# RP2040_Logic_Analyzer.net
KiCad netlist of a schematic drawn in Altium Designer
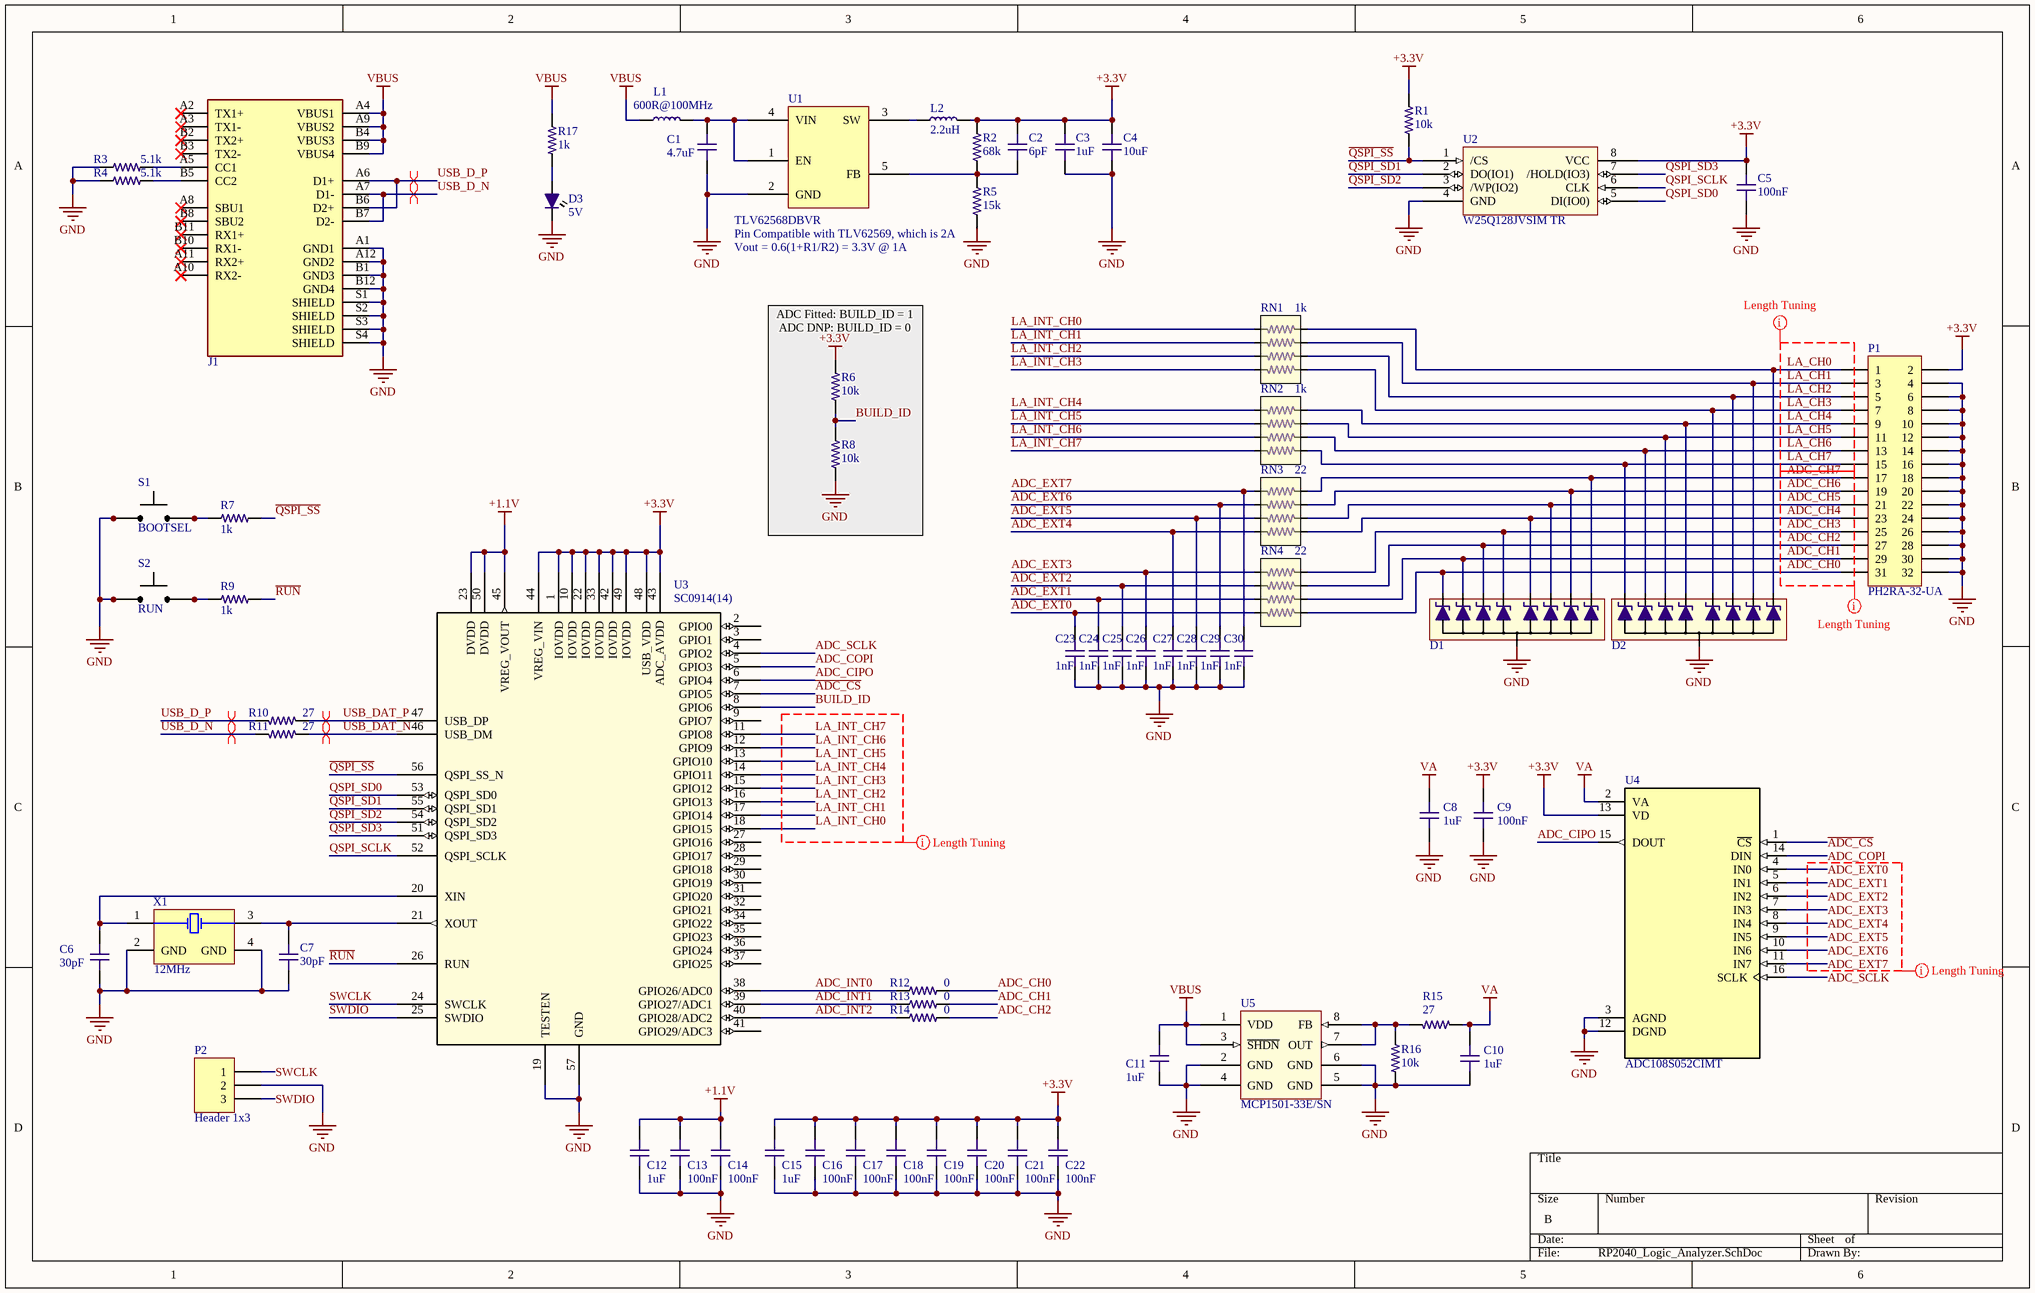
[diagram p0: RP2040_Logic_Analyzer.SchDoc]

(export (version "E")
  (design (tool "Eeschema 10.0.6"))
  (components
    (comp (ref "C1")
      (value "4.7uF")
      (footprint "C0603-HIGH-DENSITY")
      (description "Chip Capacitor, 0603, 4.7uF, 25V, X5R")
      (fields (field (name "Comment") "4.7uF, 25V, X5R, 0603"))
      (libsource (lib "Capacitors") (part "C0603 4.7uF 25V X5R"))
    )
    (comp (ref "C2")
      (value "6pF")
      (footprint "C0603-HIGH-DENSITY")
      (description "CAP CER 6PF 50V C0G/NP0 0603")
      (fields (field (name "Comment") "CL10C060DB8NNNC"))
      (libsource (lib "Capacitors") (part "C0603 6pF 50V C0G"))
    )
    (comp (ref "C3")
      (value "1uF")
      (footprint "C0603-HIGH-DENSITY")
      (description "CAP CER 1UF 25V X7R 0603")
      (fields (field (name "Comment") "C0603 1uF 25V X7R"))
      (libsource (lib "Capacitors") (part "C0603 1uF 25V X7R"))
    )
    (comp (ref "C4")
      (value "10uF")
      (footprint "C0603-HIGH-DENSITY")
      (description "Chip Capacitor, 0603, 10uF, 10V, X5R")
      (fields (field (name "Comment") "C0603 10uF 10V X5R"))
      (libsource (lib "Capacitors") (part "C0603 10uF 10V X5R"))
    )
    (comp (ref "C5")
      (value "100nF")
      (footprint "C0603-HIGH-DENSITY")
      (description "Chip Capacitor, 0603, 100nF, 25V, X7R")
      (fields (field (name "Comment") "C0603 100nF 25V X7R"))
      (libsource (lib "Capacitors") (part "C0603 100nF 25V X7R"))
    )
    (comp (ref "C6")
      (value "30pF")
      (footprint "C0402-HIGH-DENSITY")
      (description "Chip Capacitor, 0402, 30pF, 2%, 50V, C0G")
      (fields (field (name "Comment") "C0402 30pF 50V C0G"))
      (libsource (lib "Capacitors") (part "C0402 30pF 50V C0G"))
    )
    (comp (ref "C7")
      (value "30pF")
      (footprint "C0402-HIGH-DENSITY")
      (description "Chip Capacitor, 0402, 30pF, 2%, 50V, C0G")
      (fields (field (name "Comment") "C0402 30pF 50V C0G"))
      (libsource (lib "Capacitors") (part "C0402 30pF 50V C0G"))
    )
    (comp (ref "C8")
      (value "1uF")
      (footprint "C0603-HIGH-DENSITY")
      (description "CAP CER 1UF 25V X7R 0603")
      (fields (field (name "Comment") "C0603 1uF 25V X7R"))
      (libsource (lib "Capacitors") (part "C0603 1uF 25V X7R"))
    )
    (comp (ref "C9")
      (value "100nF")
      (footprint "C0603-HIGH-DENSITY")
      (description "Chip Capacitor, 0603, 100nF, 25V, X7R")
      (fields (field (name "Comment") "C0603 100nF 25V X7R"))
      (libsource (lib "Capacitors") (part "C0603 100nF 25V X7R"))
    )
    (comp (ref "C10")
      (value "1uF")
      (footprint "C0603-HIGH-DENSITY")
      (description "CAP CER 1UF 25V X7R 0603")
      (fields (field (name "Comment") "C0603 1uF 25V X7R"))
      (libsource (lib "Capacitors") (part "C0603 1uF 25V X7R"))
    )
    (comp (ref "C11")
      (value "1uF")
      (footprint "C0603-HIGH-DENSITY")
      (description "CAP CER 1UF 25V X7R 0603")
      (fields (field (name "Comment") "C0603 1uF 25V X7R"))
      (libsource (lib "Capacitors") (part "C0603 1uF 25V X7R"))
    )
    (comp (ref "C12")
      (value "1uF")
      (footprint "C0603-HIGH-DENSITY")
      (description "CAP CER 1UF 25V X7R 0603")
      (fields (field (name "Comment") "C0603 1uF 25V X7R"))
      (libsource (lib "Capacitors") (part "C0603 1uF 25V X7R"))
    )
    (comp (ref "C13")
      (value "100nF")
      (footprint "C0603-HIGH-DENSITY")
      (description "Chip Capacitor, 0603, 100nF, 25V, X7R")
      (fields (field (name "Comment") "C0603 100nF 25V X7R"))
      (libsource (lib "Capacitors") (part "C0603 100nF 25V X7R"))
    )
    (comp (ref "C14")
      (value "100nF")
      (footprint "C0603-HIGH-DENSITY")
      (description "Chip Capacitor, 0603, 100nF, 25V, X7R")
      (fields (field (name "Comment") "C0603 100nF 25V X7R"))
      (libsource (lib "Capacitors") (part "C0603 100nF 25V X7R"))
    )
    (comp (ref "C15")
      (value "1uF")
      (footprint "C0603-HIGH-DENSITY")
      (description "CAP CER 1UF 25V X7R 0603")
      (fields (field (name "Comment") "C0603 1uF 25V X7R"))
      (libsource (lib "Capacitors") (part "C0603 1uF 25V X7R"))
    )
    (comp (ref "C16")
      (value "100nF")
      (footprint "C0603-HIGH-DENSITY")
      (description "Chip Capacitor, 0603, 100nF, 25V, X7R")
      (fields (field (name "Comment") "C0603 100nF 25V X7R"))
      (libsource (lib "Capacitors") (part "C0603 100nF 25V X7R"))
    )
    (comp (ref "C17")
      (value "100nF")
      (footprint "C0603-HIGH-DENSITY")
      (description "Chip Capacitor, 0603, 100nF, 25V, X7R")
      (fields (field (name "Comment") "C0603 100nF 25V X7R"))
      (libsource (lib "Capacitors") (part "C0603 100nF 25V X7R"))
    )
    (comp (ref "C18")
      (value "100nF")
      (footprint "C0603-HIGH-DENSITY")
      (description "Chip Capacitor, 0603, 100nF, 25V, X7R")
      (fields (field (name "Comment") "C0603 100nF 25V X7R"))
      (libsource (lib "Capacitors") (part "C0603 100nF 25V X7R"))
    )
    (comp (ref "C19")
      (value "100nF")
      (footprint "C0603-HIGH-DENSITY")
      (description "Chip Capacitor, 0603, 100nF, 25V, X7R")
      (fields (field (name "Comment") "C0603 100nF 25V X7R"))
      (libsource (lib "Capacitors") (part "C0603 100nF 25V X7R"))
    )
    (comp (ref "C20")
      (value "100nF")
      (footprint "C0603-HIGH-DENSITY")
      (description "Chip Capacitor, 0603, 100nF, 25V, X7R")
      (fields (field (name "Comment") "C0603 100nF 25V X7R"))
      (libsource (lib "Capacitors") (part "C0603 100nF 25V X7R"))
    )
    (comp (ref "C21")
      (value "100nF")
      (footprint "C0603-HIGH-DENSITY")
      (description "Chip Capacitor, 0603, 100nF, 25V, X7R")
      (fields (field (name "Comment") "C0603 100nF 25V X7R"))
      (libsource (lib "Capacitors") (part "C0603 100nF 25V X7R"))
    )
    (comp (ref "C22")
      (value "100nF")
      (footprint "C0603-HIGH-DENSITY")
      (description "Chip Capacitor, 0603, 100nF, 25V, X7R")
      (fields (field (name "Comment") "C0603 100nF 25V X7R"))
      (libsource (lib "Capacitors") (part "C0603 100nF 25V X7R"))
    )
    (comp (ref "C23")
      (value "1nF")
      (footprint "C0402-IPC")
      (description "Chip Capacitor, 0402, 1nF, 25V, X7R")
      (fields (field (name "Comment") "C0402 1nF 16V X7R"))
      (libsource (lib "Capacitors") (part "C0402 1nF 16V X7R"))
    )
    (comp (ref "C24")
      (value "1nF")
      (footprint "C0402-IPC")
      (description "Chip Capacitor, 0402, 1nF, 25V, X7R")
      (fields (field (name "Comment") "C0402 1nF 16V X7R"))
      (libsource (lib "Capacitors") (part "C0402 1nF 16V X7R"))
    )
    (comp (ref "C25")
      (value "1nF")
      (footprint "C0402-IPC")
      (description "Chip Capacitor, 0402, 1nF, 25V, X7R")
      (fields (field (name "Comment") "C0402 1nF 16V X7R"))
      (libsource (lib "Capacitors") (part "C0402 1nF 16V X7R"))
    )
    (comp (ref "C26")
      (value "1nF")
      (footprint "C0402-IPC")
      (description "Chip Capacitor, 0402, 1nF, 25V, X7R")
      (fields (field (name "Comment") "C0402 1nF 16V X7R"))
      (libsource (lib "Capacitors") (part "C0402 1nF 16V X7R"))
    )
    (comp (ref "C27")
      (value "1nF")
      (footprint "C0402-IPC")
      (description "Chip Capacitor, 0402, 1nF, 25V, X7R")
      (fields (field (name "Comment") "C0402 1nF 16V X7R"))
      (libsource (lib "Capacitors") (part "C0402 1nF 16V X7R"))
    )
    (comp (ref "C28")
      (value "1nF")
      (footprint "C0402-IPC")
      (description "Chip Capacitor, 0402, 1nF, 25V, X7R")
      (fields (field (name "Comment") "C0402 1nF 16V X7R"))
      (libsource (lib "Capacitors") (part "C0402 1nF 16V X7R"))
    )
    (comp (ref "C29")
      (value "1nF")
      (footprint "C0402-IPC")
      (description "Chip Capacitor, 0402, 1nF, 25V, X7R")
      (fields (field (name "Comment") "C0402 1nF 16V X7R"))
      (libsource (lib "Capacitors") (part "C0402 1nF 16V X7R"))
    )
    (comp (ref "C30")
      (value "1nF")
      (footprint "C0402-IPC")
      (description "Chip Capacitor, 0402, 1nF, 25V, X7R")
      (fields (field (name "Comment") "C0402 1nF 16V X7R"))
      (libsource (lib "Capacitors") (part "C0402 1nF 16V X7R"))
    )
    (comp (ref "D1")
      (value "ESD8008MUTAG")
      (footprint "UDFN14_517CN_ONS")
      (description "8.1V (Typ) Clamp 16A Ipp Tvs Diode Surface Mount 14-UDFN (5.5x1.5)")
      (libsource (lib "Diodes") (part "ESD8008MUTAG"))
    )
    (comp (ref "D2")
      (value "ESD8008MUTAG")
      (footprint "UDFN14_517CN_ONS")
      (description "8.1V (Typ) Clamp 16A Ipp Tvs Diode Surface Mount 14-UDFN (5.5x1.5)")
      (libsource (lib "Diodes") (part "ESD8008MUTAG"))
    )
    (comp (ref "D3")
      (value "5V")
      (footprint "LED0603-IPC")
      (description "LED GREEN CLEAR 0603 SMD")
      (libsource (lib "Diodes") (part "LED 0603 Green"))
    )
    (comp (ref "J1")
      (value "USB C")
      (footprint "Molex USB-C")
      (fields
        (field (name "MF") "Molex")
        (field (name "DIGI-KEY_PART_NUMBER") "WM12856CT-ND")
        (field (name "MP") "1054500101")
      )
      (libsource (lib "Connectors") (part "USB C"))
    )
    (comp (ref "L1")
      (value "600R@100MHz")
      (footprint "L0603")
      (description "600 Ohms @ 100MHz 1 Ferrite Bead 0603 (1608 Metric) 500mA 380mOhm")
      (fields (field (name "Comment") "Ferrite Bead"))
      (libsource (lib "Inductors") (part "FB 0603 600R @ 100MHz"))
    )
    (comp (ref "L2")
      (value "2.2uH")
      (footprint "L1008")
      (description "2.2µH Shielded Inductor 2.05A 117mOhm Max 1008 (2520 Metric)")
      (fields (field (name "Comment") "SDEM25201B-2R2MS"))
      (libsource (lib "Inductors") (part "SDEM25201B-2R2MS"))
    )
    (comp (ref "P1")
      (value "PH2RA-32-UA")
      (footprint "Header 2X16 THT RIGHT")
      (description "Header, 16-Pin, Dual row, Right Angle")
      (libsource (lib "Connectors") (part "Header 16X2 Right Angle"))
    )
    (comp (ref "P2")
      (value "Header 1x3")
      (footprint "HEADER 1X3 TH 2.54mm")
      (description "Header, 3-Pin")
      (fields (field (name "PUBLISHER") "Altium Limited"))
      (libsource (lib "Connectors") (part "Header 1x3"))
    )
    (comp (ref "R1")
      (value "10k")
      (footprint "R0603-IPC-10K")
      (description "RES SMD 10K OHM 1% 1/10W 0603")
      (fields (field (name "Comment") "R0603 10K 1%"))
      (libsource (lib "Resistors") (part "R0603 10K 1%"))
    )
    (comp (ref "R2")
      (value "68k")
      (footprint "R0603-HIGH-DENSITY")
      (description "RES SMD 68K OHM 1% 1/5W 0603")
      (fields (field (name "Comment") "R0603 68K 1%"))
      (libsource (lib "Resistors") (part "R0603 68K 0.1%"))
    )
    (comp (ref "R3")
      (value "5.1k")
      (footprint "R0603-IPC-5.1K")
      (description "RES SMD 5.1K OHM 1% 1/10W 0603")
      (fields (field (name "Comment") "R0603 5.1K 1%"))
      (libsource (lib "Resistors") (part "R0603 5.1K 1%"))
    )
    (comp (ref "R4")
      (value "5.1k")
      (footprint "R0603-IPC-5.1K")
      (description "RES SMD 5.1K OHM 1% 1/10W 0603")
      (fields (field (name "Comment") "R0603 5.1K 1%"))
      (libsource (lib "Resistors") (part "R0603 5.1K 1%"))
    )
    (comp (ref "R5")
      (value "15k")
      (footprint "R0603-HIGH-DENSITY")
      (description "RES SMD 15K OHM 1% 1/10W 0603")
      (fields (field (name "Comment") "R0603 15K 1%"))
      (libsource (lib "Resistors") (part "R0603 15K 1%"))
    )
    (comp (ref "R6")
      (value "10k")
      (footprint "R0603-IPC-10K")
      (description "RES SMD 10K OHM 1% 1/10W 0603")
      (fields (field (name "Comment") "R0603 10K 1%"))
      (libsource (lib "Resistors") (part "R0603 10K 1%"))
    )
    (comp (ref "R7")
      (value "1k")
      (footprint "R0603-IPC-1K")
      (description "RES SMD 1K OHM 1% 1/10W 0603")
      (fields (field (name "TOLERANCE") "±1%") (field (name "Comment") "R0603 1K 1%"))
      (libsource (lib "Resistors") (part "R0603 1K 1%"))
    )
    (comp (ref "R8")
      (value "10k")
      (footprint "R0603-IPC-10K")
      (description "RES SMD 10K OHM 1% 1/10W 0603")
      (fields (field (name "Comment") "R0603 10K 1%"))
      (libsource (lib "Resistors") (part "R0603 10K 1%"))
    )
    (comp (ref "R9")
      (value "1k")
      (footprint "R0603-IPC-1K")
      (description "RES SMD 1K OHM 1% 1/10W 0603")
      (fields (field (name "TOLERANCE") "±1%") (field (name "Comment") "R0603 1K 1%"))
      (libsource (lib "Resistors") (part "R0603 1K 1%"))
    )
    (comp (ref "R10")
      (value "27")
      (footprint "R0603-HIGH-DENSITY")
      (description "RES SMD 27 OHM 1% 1/10W 0603")
      (fields (field (name "Comment") "R0603 27R 1%"))
      (libsource (lib "Resistors") (part "R0603 27R 1%"))
    )
    (comp (ref "R11")
      (value "27")
      (footprint "R0603-HIGH-DENSITY")
      (description "RES SMD 27 OHM 1% 1/10W 0603")
      (fields (field (name "Comment") "R0603 27R 1%"))
      (libsource (lib "Resistors") (part "R0603 27R 1%"))
    )
    (comp (ref "R12")
      (value "0")
      (footprint "R0402-HIGH-DENSITY")
      (description "Chip Resistor, 0402, 0 ohm jumper")
      (fields (field (name "Comment") "R0402 0R"))
      (libsource (lib "Resistors") (part "R0402 0R"))
    )
    (comp (ref "R13")
      (value "0")
      (footprint "R0402-HIGH-DENSITY")
      (description "Chip Resistor, 0402, 0 ohm jumper")
      (fields (field (name "Comment") "R0402 0R"))
      (libsource (lib "Resistors") (part "R0402 0R"))
    )
    (comp (ref "R14")
      (value "0")
      (footprint "R0402-HIGH-DENSITY")
      (description "Chip Resistor, 0402, 0 ohm jumper")
      (fields (field (name "Comment") "R0402 0R"))
      (libsource (lib "Resistors") (part "R0402 0R"))
    )
    (comp (ref "R15")
      (value "27")
      (footprint "R0603-HIGH-DENSITY")
      (description "RES SMD 27 OHM 1% 1/10W 0603")
      (fields (field (name "Comment") "R0603 27R 1%"))
      (libsource (lib "Resistors") (part "R0603 27R 1%"))
    )
    (comp (ref "R16")
      (value "10k")
      (footprint "R0603-IPC-10K")
      (description "RES SMD 10K OHM 1% 1/10W 0603")
      (fields (field (name "Comment") "R0603 10K 1%"))
      (libsource (lib "Resistors") (part "R0603 10K 1%"))
    )
    (comp (ref "R17")
      (value "1k")
      (footprint "R0603-IPC-1K")
      (description "RES SMD 1K OHM 1% 1/10W 0603")
      (fields (field (name "TOLERANCE") "±1%") (field (name "Comment") "R0603 1K 1%"))
      (libsource (lib "Resistors") (part "R0603 1K 1%"))
    )
    (comp (ref "RN1")
      (value "1k")
      (footprint "RN1206")
      (fields (field (name "Comment") "CAY16-1001F4LF"))
      (libsource (lib "Resistors") (part "RN1206 1K 1%"))
    )
    (comp (ref "RN2")
      (value "1k")
      (footprint "RN1206")
      (fields (field (name "Comment") "CAY16-1001F4LF"))
      (libsource (lib "Resistors") (part "RN1206 1K 1%"))
    )
    (comp (ref "RN3")
      (value "22")
      (footprint "RN1206")
      (fields (field (name "Comment") "YC164-FR-0722RL"))
      (libsource (lib "Resistors") (part "RN1206 22R 1%"))
    )
    (comp (ref "RN4")
      (value "22")
      (footprint "RN1206")
      (fields (field (name "Comment") "YC164-FR-0722RL"))
      (libsource (lib "Resistors") (part "RN1206 22R 1%"))
    )
    (comp (ref "S1")
      (value "BOOTSEL")
      (footprint "TL3342F260QG")
      (description "SWITCH TACTILE SPST-NO 0.05A 12V")
      (fields (field (name "MANUFACTURER PART NUMBER") "TL3342F260QG"))
      (libsource (lib "Switches") (part "SWITCH TACTILE SPST"))
    )
    (comp (ref "S2")
      (value "RUN")
      (footprint "TL3342F260QG")
      (description "SWITCH TACTILE SPST-NO 0.05A 12V")
      (fields (field (name "MANUFACTURER PART NUMBER") "TL3342F260QG"))
      (libsource (lib "Switches") (part "SWITCH TACTILE SPST"))
    )
    (comp (ref "U1")
      (value "TLV62568DBVR")
      (footprint "DBV0005A")
      (description "IC REG BUCK ADJ 1A SOT23-5")
      (libsource (lib "Integrated Circuits") (part "TLV62568"))
    )
    (comp (ref "U2")
      (value "W25Q128JVSIM TR")
      (footprint "SOIC127P790X216-8N")
      (description "NOR Flash spiFlash, 3V, 128M-bit, 4Kb Uniform Sector, DTR")
      (libsource (lib "Integrated Circuits") (part "W25Q128JV"))
    )
    (comp (ref "U3")
      (value "SC0914(14)")
      (footprint "IC57_RP2040")
      (fields
        (field (name "MANUFACTURER") "Raspberry Pi")
        (field (name "MANUFACTURER PART NUMBER") "SC0908(13)")
      )
      (libsource (lib "Integrated Circuits") (part "RP2040"))
    )
    (comp (ref "U4")
      (value "ADC108S052CIMT")
      (footprint "SOP65P640X120-16N")
      (description "10 Bit Analog to Digital Converter 8 Input 1 SAR 16-TSSOP")
      (libsource (lib "Integrated Circuits") (part "ADC108S052CIMT"))
    )
    (comp (ref "U5")
      (value "MCP1501-33E/SN")
      (footprint "SOIC127P600X175-8N")
      (description "Series Voltage Reference IC Fixed 3.3V V ±0.1% 20 mA 8-SOIC")
      (libsource (lib "Integrated Circuits") (part "MCP1501-33E/SN"))
    )
    (comp (ref "X1")
      (value "ABM8G-12.000MHZ-18-D2Y-T")
      (footprint "ABRACON_ABM8G_V")
      (fields
        (field (name "TOLERANCE") "20PPM")
        (field (name "MANUFACTURER") "ABRACON")
        (field (name "FREQUENCY") "12MHz")
      )
      (libsource (lib "Altium Content Vault") (part "XTAL-1-3-4"))
    )
  )
  (nets
    (net (code "1") (name "+1.1V") (class "Default")
      (node (ref "C12") (pin "2") (pintype "passive"))
      (node (ref "C13") (pin "2") (pintype "passive"))
      (node (ref "C14") (pin "2") (pintype "passive"))
      (node (ref "U3") (pin "23") (pinfunction "DVDD_23") (pintype "power_in"))
      (node (ref "U3") (pin "45") (pinfunction "VREG_VOUT_45") (pintype "output"))
      (node (ref "U3") (pin "50") (pinfunction "DVDD_50") (pintype "power_in"))
    )
    (net (code "2") (name "+3.3V") (class "Default")
      (node (ref "C15") (pin "2") (pintype "passive"))
      (node (ref "C16") (pin "2") (pintype "passive"))
      (node (ref "C17") (pin "2") (pintype "passive"))
      (node (ref "C18") (pin "2") (pintype "passive"))
      (node (ref "C19") (pin "2") (pintype "passive"))
      (node (ref "C2") (pin "2") (pintype "passive"))
      (node (ref "C20") (pin "2") (pintype "passive"))
      (node (ref "C21") (pin "2") (pintype "passive"))
      (node (ref "C22") (pin "2") (pintype "passive"))
      (node (ref "C3") (pin "2") (pintype "passive"))
      (node (ref "C4") (pin "2") (pintype "passive"))
      (node (ref "C5") (pin "2") (pintype "passive"))
      (node (ref "C9") (pin "2") (pintype "passive"))
      (node (ref "L2") (pin "2") (pintype "passive"))
      (node (ref "P1") (pin "2") (pinfunction "2_2") (pintype "passive"))
      (node (ref "R1") (pin "2") (pintype "passive"))
      (node (ref "R2") (pin "2") (pintype "passive"))
      (node (ref "R6") (pin "2") (pintype "passive"))
      (node (ref "U2") (pin "8") (pinfunction "VCC_8") (pintype "power_in"))
      (node (ref "U3") (pin "1") (pinfunction "IOVDD_1") (pintype "power_in"))
      (node (ref "U3") (pin "10") (pinfunction "IOVDD_10") (pintype "power_in"))
      (node (ref "U3") (pin "22") (pinfunction "IOVDD_22") (pintype "power_in"))
      (node (ref "U3") (pin "33") (pinfunction "IOVDD_33") (pintype "power_in"))
      (node (ref "U3") (pin "42") (pinfunction "IOVDD_42") (pintype "power_in"))
      (node (ref "U3") (pin "43") (pinfunction "ADC_AVDD_43") (pintype "power_in"))
      (node (ref "U3") (pin "44") (pinfunction "VREG_VIN_44") (pintype "passive"))
      (node (ref "U3") (pin "48") (pinfunction "USB_VDD_48") (pintype "power_in"))
      (node (ref "U3") (pin "49") (pinfunction "IOVDD_49") (pintype "power_in"))
      (node (ref "U4") (pin "13") (pinfunction "VD_13") (pintype "power_in"))
    )
    (net (code "3") (name "/ADC_CH0") (class "Default")
      (node (ref "D1") (pin "1") (pinfunction "1_1") (pintype "passive"))
      (node (ref "P1") (pin "31") (pinfunction "31_31") (pintype "passive"))
      (node (ref "R12") (pin "2") (pintype "passive"))
      (node (ref "RN4") (pin "5") (pintype "passive"))
    )
    (net (code "4") (name "/ADC_CH1") (class "Default")
      (node (ref "D1") (pin "2") (pinfunction "2_2") (pintype "passive"))
      (node (ref "P1") (pin "29") (pinfunction "29_29") (pintype "passive"))
      (node (ref "R13") (pin "2") (pintype "passive"))
      (node (ref "RN4") (pin "6") (pintype "passive"))
    )
    (net (code "5") (name "/ADC_CH2") (class "Default")
      (node (ref "D1") (pin "4") (pinfunction "4_4") (pintype "passive"))
      (node (ref "P1") (pin "27") (pinfunction "27_27") (pintype "passive"))
      (node (ref "R14") (pin "2") (pintype "passive"))
      (node (ref "RN4") (pin "7") (pintype "passive"))
    )
    (net (code "6") (name "/ADC_CH3") (class "Default")
      (node (ref "D1") (pin "5") (pinfunction "5_5") (pintype "passive"))
      (node (ref "P1") (pin "25") (pinfunction "25_25") (pintype "passive"))
      (node (ref "RN4") (pin "8") (pintype "passive"))
    )
    (net (code "7") (name "/ADC_CH4") (class "Default")
      (node (ref "D1") (pin "7") (pinfunction "7_7") (pintype "passive"))
      (node (ref "P1") (pin "23") (pinfunction "23_23") (pintype "passive"))
      (node (ref "RN3") (pin "5") (pintype "passive"))
    )
    (net (code "8") (name "/ADC_CH5") (class "Default")
      (node (ref "D1") (pin "8") (pinfunction "8_8") (pintype "passive"))
      (node (ref "P1") (pin "21") (pinfunction "21_21") (pintype "passive"))
      (node (ref "RN3") (pin "6") (pintype "passive"))
    )
    (net (code "9") (name "/ADC_CH6") (class "Default")
      (node (ref "D1") (pin "10") (pinfunction "10_10") (pintype "passive"))
      (node (ref "P1") (pin "19") (pinfunction "19_19") (pintype "passive"))
      (node (ref "RN3") (pin "7") (pintype "passive"))
    )
    (net (code "10") (name "/ADC_CH7") (class "Default")
      (node (ref "D1") (pin "11") (pinfunction "11_11") (pintype "passive"))
      (node (ref "P1") (pin "17") (pinfunction "17_17") (pintype "passive"))
      (node (ref "RN3") (pin "8") (pintype "passive"))
    )
    (net (code "11") (name "/ADC_CIPO") (class "Default")
      (node (ref "U3") (pin "6") (pinfunction "GPIO4_6") (pintype "bidirectional"))
      (node (ref "U4") (pin "15") (pinfunction "DOUT_15") (pintype "output"))
    )
    (net (code "12") (name "/ADC_COPI") (class "Default")
      (node (ref "U3") (pin "5") (pinfunction "GPIO3_5") (pintype "bidirectional"))
      (node (ref "U4") (pin "14") (pinfunction "DIN_14") (pintype "input"))
    )
    (net (code "13") (name "/ADC_EXT0") (class "Default")
      (node (ref "C23") (pin "2") (pintype "passive"))
      (node (ref "RN4") (pin "4") (pintype "passive"))
      (node (ref "U4") (pin "4") (pinfunction "IN0_4") (pintype "input"))
    )
    (net (code "14") (name "/ADC_EXT1") (class "Default")
      (node (ref "C24") (pin "2") (pintype "passive"))
      (node (ref "RN4") (pin "3") (pintype "passive"))
      (node (ref "U4") (pin "5") (pinfunction "IN1_5") (pintype "input"))
    )
    (net (code "15") (name "/ADC_EXT2") (class "Default")
      (node (ref "C25") (pin "2") (pintype "passive"))
      (node (ref "RN4") (pin "2") (pintype "passive"))
      (node (ref "U4") (pin "6") (pinfunction "IN2_6") (pintype "input"))
    )
    (net (code "16") (name "/ADC_EXT3") (class "Default")
      (node (ref "C26") (pin "2") (pintype "passive"))
      (node (ref "RN4") (pin "1") (pintype "passive"))
      (node (ref "U4") (pin "7") (pinfunction "IN3_7") (pintype "input"))
    )
    (net (code "17") (name "/ADC_EXT4") (class "Default")
      (node (ref "C27") (pin "2") (pintype "passive"))
      (node (ref "RN3") (pin "4") (pintype "passive"))
      (node (ref "U4") (pin "8") (pinfunction "IN4_8") (pintype "input"))
    )
    (net (code "18") (name "/ADC_EXT5") (class "Default")
      (node (ref "C28") (pin "2") (pintype "passive"))
      (node (ref "RN3") (pin "3") (pintype "passive"))
      (node (ref "U4") (pin "9") (pinfunction "IN5_9") (pintype "input"))
    )
    (net (code "19") (name "/ADC_EXT6") (class "Default")
      (node (ref "C29") (pin "2") (pintype "passive"))
      (node (ref "RN3") (pin "2") (pintype "passive"))
      (node (ref "U4") (pin "10") (pinfunction "IN6_10") (pintype "input"))
    )
    (net (code "20") (name "/ADC_EXT7") (class "Default")
      (node (ref "C30") (pin "2") (pintype "passive"))
      (node (ref "RN3") (pin "1") (pintype "passive"))
      (node (ref "U4") (pin "11") (pinfunction "IN7_11") (pintype "input"))
    )
    (net (code "21") (name "/ADC_INT0") (class "Default")
      (node (ref "R12") (pin "1") (pintype "passive"))
      (node (ref "U3") (pin "38") (pinfunction "GPIO26/ADC0_38") (pintype "bidirectional"))
    )
    (net (code "22") (name "/ADC_INT1") (class "Default")
      (node (ref "R13") (pin "1") (pintype "passive"))
      (node (ref "U3") (pin "39") (pinfunction "GPIO27/ADC1_39") (pintype "bidirectional"))
    )
    (net (code "23") (name "/ADC_INT2") (class "Default")
      (node (ref "R14") (pin "1") (pintype "passive"))
      (node (ref "U3") (pin "40") (pinfunction "GPIO28/ADC2_40") (pintype "bidirectional"))
    )
    (net (code "24") (name "/ADC_SCLK") (class "Default")
      (node (ref "U3") (pin "4") (pinfunction "GPIO2_4") (pintype "bidirectional"))
      (node (ref "U4") (pin "16") (pinfunction "SCLK_16") (pintype "input"))
    )
    (net (code "25") (name "/BUILD_ID") (class "Default")
      (node (ref "R6") (pin "1") (pintype "passive"))
      (node (ref "R8") (pin "2") (pintype "passive"))
      (node (ref "U3") (pin "8") (pinfunction "GPIO6_8") (pintype "bidirectional"))
    )
    (net (code "26") (name "/LA_CH0") (class "Default")
      (node (ref "D2") (pin "11") (pinfunction "11_11") (pintype "passive"))
      (node (ref "P1") (pin "1") (pinfunction "1_1") (pintype "passive"))
      (node (ref "RN1") (pin "4") (pintype "passive"))
    )
    (net (code "27") (name "/LA_CH1") (class "Default")
      (node (ref "D2") (pin "10") (pinfunction "10_10") (pintype "passive"))
      (node (ref "P1") (pin "3") (pinfunction "3_3") (pintype "passive"))
      (node (ref "RN1") (pin "3") (pintype "passive"))
    )
    (net (code "28") (name "/LA_CH2") (class "Default")
      (node (ref "D2") (pin "8") (pinfunction "8_8") (pintype "passive"))
      (node (ref "P1") (pin "5") (pinfunction "5_5") (pintype "passive"))
      (node (ref "RN1") (pin "2") (pintype "passive"))
    )
    (net (code "29") (name "/LA_CH3") (class "Default")
      (node (ref "D2") (pin "7") (pinfunction "7_7") (pintype "passive"))
      (node (ref "P1") (pin "7") (pinfunction "7_7") (pintype "passive"))
      (node (ref "RN1") (pin "1") (pintype "passive"))
    )
    (net (code "30") (name "/LA_CH4") (class "Default")
      (node (ref "D2") (pin "5") (pinfunction "5_5") (pintype "passive"))
      (node (ref "P1") (pin "9") (pinfunction "9_9") (pintype "passive"))
      (node (ref "RN2") (pin "4") (pintype "passive"))
    )
    (net (code "31") (name "/LA_CH5") (class "Default")
      (node (ref "D2") (pin "4") (pinfunction "4_4") (pintype "passive"))
      (node (ref "P1") (pin "11") (pinfunction "11_11") (pintype "passive"))
      (node (ref "RN2") (pin "3") (pintype "passive"))
    )
    (net (code "32") (name "/LA_CH6") (class "Default")
      (node (ref "D2") (pin "2") (pinfunction "2_2") (pintype "passive"))
      (node (ref "P1") (pin "13") (pinfunction "13_13") (pintype "passive"))
      (node (ref "RN2") (pin "2") (pintype "passive"))
    )
    (net (code "33") (name "/LA_CH7") (class "Default")
      (node (ref "D2") (pin "1") (pinfunction "1_1") (pintype "passive"))
      (node (ref "P1") (pin "15") (pinfunction "15_15") (pintype "passive"))
      (node (ref "RN2") (pin "1") (pintype "passive"))
    )
    (net (code "34") (name "/LA_INT_CH0") (class "Default")
      (node (ref "RN1") (pin "5") (pintype "passive"))
      (node (ref "U3") (pin "18") (pinfunction "GPIO15_18") (pintype "bidirectional"))
    )
    (net (code "35") (name "/LA_INT_CH1") (class "Default")
      (node (ref "RN1") (pin "6") (pintype "passive"))
      (node (ref "U3") (pin "17") (pinfunction "GPIO14_17") (pintype "bidirectional"))
    )
    (net (code "36") (name "/LA_INT_CH2") (class "Default")
      (node (ref "RN1") (pin "7") (pintype "passive"))
      (node (ref "U3") (pin "16") (pinfunction "GPIO13_16") (pintype "bidirectional"))
    )
    (net (code "37") (name "/LA_INT_CH3") (class "Default")
      (node (ref "RN1") (pin "8") (pintype "passive"))
      (node (ref "U3") (pin "15") (pinfunction "GPIO12_15") (pintype "bidirectional"))
    )
    (net (code "38") (name "/LA_INT_CH4") (class "Default")
      (node (ref "RN2") (pin "5") (pintype "passive"))
      (node (ref "U3") (pin "14") (pinfunction "GPIO11_14") (pintype "bidirectional"))
    )
    (net (code "39") (name "/LA_INT_CH5") (class "Default")
      (node (ref "RN2") (pin "6") (pintype "passive"))
      (node (ref "U3") (pin "13") (pinfunction "GPIO10_13") (pintype "bidirectional"))
    )
    (net (code "40") (name "/LA_INT_CH6") (class "Default")
      (node (ref "RN2") (pin "7") (pintype "passive"))
      (node (ref "U3") (pin "12") (pinfunction "GPIO9_12") (pintype "bidirectional"))
    )
    (net (code "41") (name "/LA_INT_CH7") (class "Default")
      (node (ref "RN2") (pin "8") (pintype "passive"))
      (node (ref "U3") (pin "11") (pinfunction "GPIO8_11") (pintype "bidirectional"))
    )
    (net (code "42") (name "/QSPI_SCLK") (class "Default")
      (node (ref "U2") (pin "6") (pinfunction "CLK_6") (pintype "input"))
      (node (ref "U3") (pin "52") (pinfunction "QSPI_SCLK_52") (pintype "passive"))
    )
    (net (code "43") (name "/QSPI_SD0") (class "Default")
      (node (ref "U2") (pin "5") (pinfunction "DI(IO0)_5") (pintype "bidirectional"))
      (node (ref "U3") (pin "53") (pinfunction "QSPI_SD0_53") (pintype "bidirectional"))
    )
    (net (code "44") (name "/QSPI_SD1") (class "Default")
      (node (ref "U2") (pin "2") (pinfunction "DO(IO1)_2") (pintype "bidirectional"))
      (node (ref "U3") (pin "55") (pinfunction "QSPI_SD1_55") (pintype "bidirectional"))
    )
    (net (code "45") (name "/QSPI_SD2") (class "Default")
      (node (ref "U2") (pin "3") (pinfunction "/WP(IO2)_3") (pintype "bidirectional"))
      (node (ref "U3") (pin "54") (pinfunction "QSPI_SD2_54") (pintype "bidirectional"))
    )
    (net (code "46") (name "/QSPI_SD3") (class "Default")
      (node (ref "U2") (pin "7") (pinfunction "/HOLD(IO3)_7") (pintype "bidirectional"))
      (node (ref "U3") (pin "51") (pinfunction "QSPI_SD3_51") (pintype "bidirectional"))
    )
    (net (code "47") (name "/SWCLK") (class "Default")
      (node (ref "P2") (pin "1") (pinfunction "1_1") (pintype "passive"))
      (node (ref "U3") (pin "24") (pinfunction "SWCLK_24") (pintype "passive"))
    )
    (net (code "48") (name "/SWDIO") (class "Default")
      (node (ref "P2") (pin "3") (pinfunction "3_3") (pintype "passive"))
      (node (ref "U3") (pin "25") (pinfunction "SWDIO_25") (pintype "passive"))
    )
    (net (code "49") (name "/USB_DAT_N") (class "Default")
      (node (ref "R11") (pin "1") (pintype "passive"))
      (node (ref "U3") (pin "46") (pinfunction "USB_DM_46") (pintype "passive"))
    )
    (net (code "50") (name "/USB_DAT_P") (class "Default")
      (node (ref "R10") (pin "1") (pintype "passive"))
      (node (ref "U3") (pin "47") (pinfunction "USB_DP_47") (pintype "passive"))
    )
    (net (code "51") (name "/USB_D_N") (class "Default")
      (node (ref "J1") (pin "A7") (pinfunction "D1-_A7") (pintype "passive"))
      (node (ref "J1") (pin "B7") (pinfunction "D2-_B7") (pintype "passive"))
      (node (ref "R11") (pin "2") (pintype "passive"))
    )
    (net (code "52") (name "/USB_D_P") (class "Default")
      (node (ref "J1") (pin "A6") (pinfunction "D1+_A6") (pintype "passive"))
      (node (ref "J1") (pin "B6") (pinfunction "D2+_B6") (pintype "passive"))
      (node (ref "R10") (pin "2") (pintype "passive"))
    )
    (net (code "53") (name "/~{ADC_CS}") (class "Default")
      (node (ref "U3") (pin "7") (pinfunction "GPIO5_7") (pintype "bidirectional"))
      (node (ref "U4") (pin "1") (pinfunction "~{CS}_1") (pintype "input"))
    )
    (net (code "54") (name "/~{QSPI_SS}") (class "Default")
      (node (ref "R1") (pin "1") (pintype "passive"))
      (node (ref "R7") (pin "2") (pintype "passive"))
      (node (ref "U2") (pin "1") (pinfunction "/CS_1") (pintype "input"))
      (node (ref "U3") (pin "56") (pinfunction "QSPI_SS_N_56") (pintype "passive"))
    )
    (net (code "55") (name "/~{RUN}") (class "Default")
      (node (ref "R9") (pin "2") (pintype "passive"))
      (node (ref "U3") (pin "26") (pinfunction "RUN_26") (pintype "passive"))
    )
    (net (code "56") (name "GND") (class "Default")
      (node (ref "C1") (pin "1") (pintype "passive"))
      (node (ref "C10") (pin "1") (pintype "passive"))
      (node (ref "C11") (pin "1") (pintype "passive"))
      (node (ref "C12") (pin "1") (pintype "passive"))
      (node (ref "C13") (pin "1") (pintype "passive"))
      (node (ref "C14") (pin "1") (pintype "passive"))
      (node (ref "C15") (pin "1") (pintype "passive"))
      (node (ref "C16") (pin "1") (pintype "passive"))
      (node (ref "C17") (pin "1") (pintype "passive"))
      (node (ref "C18") (pin "1") (pintype "passive"))
      (node (ref "C19") (pin "1") (pintype "passive"))
      (node (ref "C20") (pin "1") (pintype "passive"))
      (node (ref "C21") (pin "1") (pintype "passive"))
      (node (ref "C22") (pin "1") (pintype "passive"))
      (node (ref "C23") (pin "1") (pintype "passive"))
      (node (ref "C24") (pin "1") (pintype "passive"))
      (node (ref "C25") (pin "1") (pintype "passive"))
      (node (ref "C26") (pin "1") (pintype "passive"))
      (node (ref "C27") (pin "1") (pintype "passive"))
      (node (ref "C28") (pin "1") (pintype "passive"))
      (node (ref "C29") (pin "1") (pintype "passive"))
      (node (ref "C3") (pin "1") (pintype "passive"))
      (node (ref "C30") (pin "1") (pintype "passive"))
      (node (ref "C4") (pin "1") (pintype "passive"))
      (node (ref "C5") (pin "1") (pintype "passive"))
      (node (ref "C6") (pin "1") (pintype "passive"))
      (node (ref "C7") (pin "1") (pintype "passive"))
      (node (ref "C8") (pin "1") (pintype "passive"))
      (node (ref "C9") (pin "1") (pintype "passive"))
      (node (ref "D1") (pin "3") (pinfunction "3_3") (pintype "passive"))
      (node (ref "D2") (pin "3") (pinfunction "3_3") (pintype "passive"))
      (node (ref "D3") (pin "K") (pintype "passive"))
      (node (ref "J1") (pin "A1") (pinfunction "GND1_A1") (pintype "passive"))
      (node (ref "J1") (pin "A12") (pinfunction "GND2_A12") (pintype "passive"))
      (node (ref "J1") (pin "B1") (pinfunction "GND3_B1") (pintype "passive"))
      (node (ref "J1") (pin "B12") (pinfunction "GND4_B12") (pintype "passive"))
      (node (ref "J1") (pin "S1") (pinfunction "SHIELD_S1") (pintype "passive"))
      (node (ref "J1") (pin "S2") (pinfunction "SHIELD_S2") (pintype "passive"))
      (node (ref "J1") (pin "S3") (pinfunction "SHIELD_S3") (pintype "passive"))
      (node (ref "J1") (pin "S4") (pinfunction "SHIELD_S4") (pintype "passive"))
      (node (ref "P1") (pin "10") (pinfunction "10_10") (pintype "passive"))
      (node (ref "P1") (pin "12") (pinfunction "12_12") (pintype "passive"))
      (node (ref "P1") (pin "14") (pinfunction "14_14") (pintype "passive"))
      (node (ref "P1") (pin "16") (pinfunction "16_16") (pintype "passive"))
      (node (ref "P1") (pin "18") (pinfunction "18_18") (pintype "passive"))
      (node (ref "P1") (pin "20") (pinfunction "20_20") (pintype "passive"))
      (node (ref "P1") (pin "22") (pinfunction "22_22") (pintype "passive"))
      (node (ref "P1") (pin "24") (pinfunction "24_24") (pintype "passive"))
      (node (ref "P1") (pin "26") (pinfunction "26_26") (pintype "passive"))
      (node (ref "P1") (pin "28") (pinfunction "28_28") (pintype "passive"))
      (node (ref "P1") (pin "30") (pinfunction "30_30") (pintype "passive"))
      (node (ref "P1") (pin "32") (pinfunction "32_32") (pintype "passive"))
      (node (ref "P1") (pin "4") (pinfunction "4_4") (pintype "passive"))
      (node (ref "P1") (pin "6") (pinfunction "6_6") (pintype "passive"))
      (node (ref "P1") (pin "8") (pinfunction "8_8") (pintype "passive"))
      (node (ref "P2") (pin "2") (pinfunction "2_2") (pintype "passive"))
      (node (ref "R16") (pin "1") (pintype "passive"))
      (node (ref "R3") (pin "1") (pintype "passive"))
      (node (ref "R4") (pin "1") (pintype "passive"))
      (node (ref "R5") (pin "1") (pintype "passive"))
      (node (ref "R8") (pin "1") (pintype "passive"))
      (node (ref "S1") (pin "3") (pinfunction "3_3") (pintype "passive"))
      (node (ref "S1") (pin "4") (pinfunction "4_4") (pintype "passive"))
      (node (ref "S2") (pin "3") (pinfunction "3_3") (pintype "passive"))
      (node (ref "S2") (pin "4") (pinfunction "4_4") (pintype "passive"))
      (node (ref "U1") (pin "2") (pinfunction "GND_2") (pintype "passive"))
      (node (ref "U2") (pin "4") (pinfunction "GND_4") (pintype "power_in"))
      (node (ref "U3") (pin "19") (pinfunction "TESTEN_19") (pintype "passive"))
      (node (ref "U3") (pin "57") (pinfunction "GND_57") (pintype "passive"))
      (node (ref "U4") (pin "12") (pinfunction "DGND_12") (pintype "power_in"))
      (node (ref "U4") (pin "3") (pinfunction "AGND_3") (pintype "power_in"))
      (node (ref "U5") (pin "2") (pinfunction "GND_2") (pintype "power_in"))
      (node (ref "U5") (pin "4") (pinfunction "GND_4") (pintype "power_in"))
      (node (ref "U5") (pin "5") (pinfunction "GND_5") (pintype "power_in"))
      (node (ref "U5") (pin "6") (pinfunction "GND_6") (pintype "power_in"))
      (node (ref "X1") (pin "2") (pinfunction "GND_2") (pintype "power_in"))
      (node (ref "X1") (pin "4") (pinfunction "GND_4") (pintype "power_in"))
    )
    (net (code "57") (name "Net-(D3-PadA)") (class "Default")
      (node (ref "D3") (pin "A") (pintype "passive"))
      (node (ref "R17") (pin "1") (pintype "passive"))
    )
    (net (code "58") (name "Net-(J1-CC1)") (class "Default")
      (node (ref "J1") (pin "A5") (pinfunction "CC1_A5") (pintype "passive"))
      (node (ref "R3") (pin "2") (pintype "passive"))
    )
    (net (code "59") (name "Net-(J1-CC2)") (class "Default")
      (node (ref "J1") (pin "B5") (pinfunction "CC2_B5") (pintype "passive"))
      (node (ref "R4") (pin "2") (pintype "passive"))
    )
    (net (code "60") (name "Net-(R7-Pad1)") (class "Default")
      (node (ref "R7") (pin "1") (pintype "passive"))
      (node (ref "S1") (pin "1") (pinfunction "1_1") (pintype "passive"))
      (node (ref "S1") (pin "2") (pinfunction "2_2") (pintype "passive"))
    )
    (net (code "61") (name "Net-(R9-Pad1)") (class "Default")
      (node (ref "R9") (pin "1") (pintype "passive"))
      (node (ref "S2") (pin "1") (pinfunction "1_1") (pintype "passive"))
      (node (ref "S2") (pin "2") (pinfunction "2_2") (pintype "passive"))
    )
    (net (code "62") (name "Net-(U1-EN)") (class "Default")
      (node (ref "C1") (pin "2") (pintype "passive"))
      (node (ref "L1") (pin "2") (pintype "passive"))
      (node (ref "U1") (pin "1") (pinfunction "EN_1") (pintype "passive"))
      (node (ref "U1") (pin "4") (pinfunction "VIN_4") (pintype "passive"))
    )
    (net (code "63") (name "Net-(U1-FB)") (class "Default")
      (node (ref "C2") (pin "1") (pintype "passive"))
      (node (ref "R2") (pin "1") (pintype "passive"))
      (node (ref "R5") (pin "2") (pintype "passive"))
      (node (ref "U1") (pin "5") (pinfunction "FB_5") (pintype "passive"))
    )
    (net (code "64") (name "Net-(U1-SW)") (class "Default")
      (node (ref "L2") (pin "1") (pintype "passive"))
      (node (ref "U1") (pin "3") (pinfunction "SW_3") (pintype "passive"))
    )
    (net (code "65") (name "Net-(U3-XIN)") (class "Default")
      (node (ref "C6") (pin "2") (pintype "passive"))
      (node (ref "U3") (pin "20") (pinfunction "XIN_20") (pintype "passive"))
      (node (ref "X1") (pin "1") (pinfunction "X1_1") (pintype "passive"))
    )
    (net (code "66") (name "Net-(U3-XOUT)") (class "Default")
      (node (ref "C7") (pin "2") (pintype "passive"))
      (node (ref "U3") (pin "21") (pinfunction "XOUT_21") (pintype "output"))
      (node (ref "X1") (pin "3") (pinfunction "X2_3") (pintype "passive"))
    )
    (net (code "67") (name "Net-(U5-FB)") (class "Default")
      (node (ref "R15") (pin "2") (pintype "passive"))
      (node (ref "R16") (pin "2") (pintype "passive"))
      (node (ref "U5") (pin "7") (pinfunction "OUT_7") (pintype "output"))
      (node (ref "U5") (pin "8") (pinfunction "FB_8") (pintype "input"))
    )
    (net (code "68") (name "VA") (class "Default")
      (node (ref "C10") (pin "2") (pintype "passive"))
      (node (ref "C8") (pin "2") (pintype "passive"))
      (node (ref "R15") (pin "1") (pintype "passive"))
      (node (ref "U4") (pin "2") (pinfunction "VA_2") (pintype "power_in"))
    )
    (net (code "69") (name "VBUS") (class "Default")
      (node (ref "C11") (pin "2") (pintype "passive"))
      (node (ref "J1") (pin "A4") (pinfunction "VBUS1_A4") (pintype "passive"))
      (node (ref "J1") (pin "A9") (pinfunction "VBUS2_A9") (pintype "passive"))
      (node (ref "J1") (pin "B4") (pinfunction "VBUS3_B4") (pintype "passive"))
      (node (ref "J1") (pin "B9") (pinfunction "VBUS4_B9") (pintype "passive"))
      (node (ref "L1") (pin "1") (pintype "passive"))
      (node (ref "R17") (pin "2") (pintype "passive"))
      (node (ref "U5") (pin "1") (pinfunction "VDD_1") (pintype "power_in"))
      (node (ref "U5") (pin "3") (pinfunction "~{SHDN}_3") (pintype "input"))
    )
    (net (code "70") (name "unconnected-(J1-RX1+-PadB11)") (class "Default")
      (node (ref "J1") (pin "B11") (pinfunction "RX1+_B11") (pintype "passive+no_connect"))
    )
    (net (code "71") (name "unconnected-(J1-RX1--PadB10)") (class "Default")
      (node (ref "J1") (pin "B10") (pinfunction "RX1-_B10") (pintype "passive+no_connect"))
    )
    (net (code "72") (name "unconnected-(J1-RX2+-PadA11)") (class "Default")
      (node (ref "J1") (pin "A11") (pinfunction "RX2+_A11") (pintype "passive+no_connect"))
    )
    (net (code "73") (name "unconnected-(J1-RX2--PadA10)") (class "Default")
      (node (ref "J1") (pin "A10") (pinfunction "RX2-_A10") (pintype "passive+no_connect"))
    )
    (net (code "74") (name "unconnected-(J1-SBU1-PadA8)") (class "Default")
      (node (ref "J1") (pin "A8") (pinfunction "SBU1_A8") (pintype "passive+no_connect"))
    )
    (net (code "75") (name "unconnected-(J1-SBU2-PadB8)") (class "Default")
      (node (ref "J1") (pin "B8") (pinfunction "SBU2_B8") (pintype "passive+no_connect"))
    )
    (net (code "76") (name "unconnected-(J1-TX1+-PadA2)") (class "Default")
      (node (ref "J1") (pin "A2") (pinfunction "TX1+_A2") (pintype "passive+no_connect"))
    )
    (net (code "77") (name "unconnected-(J1-TX1--PadA3)") (class "Default")
      (node (ref "J1") (pin "A3") (pinfunction "TX1-_A3") (pintype "passive+no_connect"))
    )
    (net (code "78") (name "unconnected-(J1-TX2+-PadB2)") (class "Default")
      (node (ref "J1") (pin "B2") (pinfunction "TX2+_B2") (pintype "passive+no_connect"))
    )
    (net (code "79") (name "unconnected-(J1-TX2--PadB3)") (class "Default")
      (node (ref "J1") (pin "B3") (pinfunction "TX2-_B3") (pintype "passive+no_connect"))
    )
    (net (code "80") (name "unconnected-(U3-GPIO0-Pad2)") (class "Default")
      (node (ref "U3") (pin "2") (pinfunction "GPIO0_2") (pintype "bidirectional"))
    )
    (net (code "81") (name "unconnected-(U3-GPIO1-Pad3)") (class "Default")
      (node (ref "U3") (pin "3") (pinfunction "GPIO1_3") (pintype "bidirectional"))
    )
    (net (code "82") (name "unconnected-(U3-GPIO7-Pad9)") (class "Default")
      (node (ref "U3") (pin "9") (pinfunction "GPIO7_9") (pintype "bidirectional"))
    )
    (net (code "83") (name "unconnected-(U3-GPIO16-Pad27)") (class "Default")
      (node (ref "U3") (pin "27") (pinfunction "GPIO16_27") (pintype "bidirectional"))
    )
    (net (code "84") (name "unconnected-(U3-GPIO17-Pad28)") (class "Default")
      (node (ref "U3") (pin "28") (pinfunction "GPIO17_28") (pintype "bidirectional"))
    )
    (net (code "85") (name "unconnected-(U3-GPIO18-Pad29)") (class "Default")
      (node (ref "U3") (pin "29") (pinfunction "GPIO18_29") (pintype "bidirectional"))
    )
    (net (code "86") (name "unconnected-(U3-GPIO19-Pad30)") (class "Default")
      (node (ref "U3") (pin "30") (pinfunction "GPIO19_30") (pintype "bidirectional"))
    )
    (net (code "87") (name "unconnected-(U3-GPIO20-Pad31)") (class "Default")
      (node (ref "U3") (pin "31") (pinfunction "GPIO20_31") (pintype "bidirectional"))
    )
    (net (code "88") (name "unconnected-(U3-GPIO21-Pad32)") (class "Default")
      (node (ref "U3") (pin "32") (pinfunction "GPIO21_32") (pintype "bidirectional"))
    )
    (net (code "89") (name "unconnected-(U3-GPIO22-Pad34)") (class "Default")
      (node (ref "U3") (pin "34") (pinfunction "GPIO22_34") (pintype "bidirectional"))
    )
    (net (code "90") (name "unconnected-(U3-GPIO23-Pad35)") (class "Default")
      (node (ref "U3") (pin "35") (pinfunction "GPIO23_35") (pintype "bidirectional"))
    )
    (net (code "91") (name "unconnected-(U3-GPIO24-Pad36)") (class "Default")
      (node (ref "U3") (pin "36") (pinfunction "GPIO24_36") (pintype "bidirectional"))
    )
    (net (code "92") (name "unconnected-(U3-GPIO25-Pad37)") (class "Default")
      (node (ref "U3") (pin "37") (pinfunction "GPIO25_37") (pintype "bidirectional"))
    )
    (net (code "93") (name "unconnected-(U3-GPIO29{slash}ADC3-Pad41)") (class "Default")
      (node (ref "U3") (pin "41") (pinfunction "GPIO29/ADC3_41") (pintype "bidirectional"))
    )
  )
)
